# BiodataModular_008_SMD.net
KiCad netlist of a schematic drawn in EAGLE
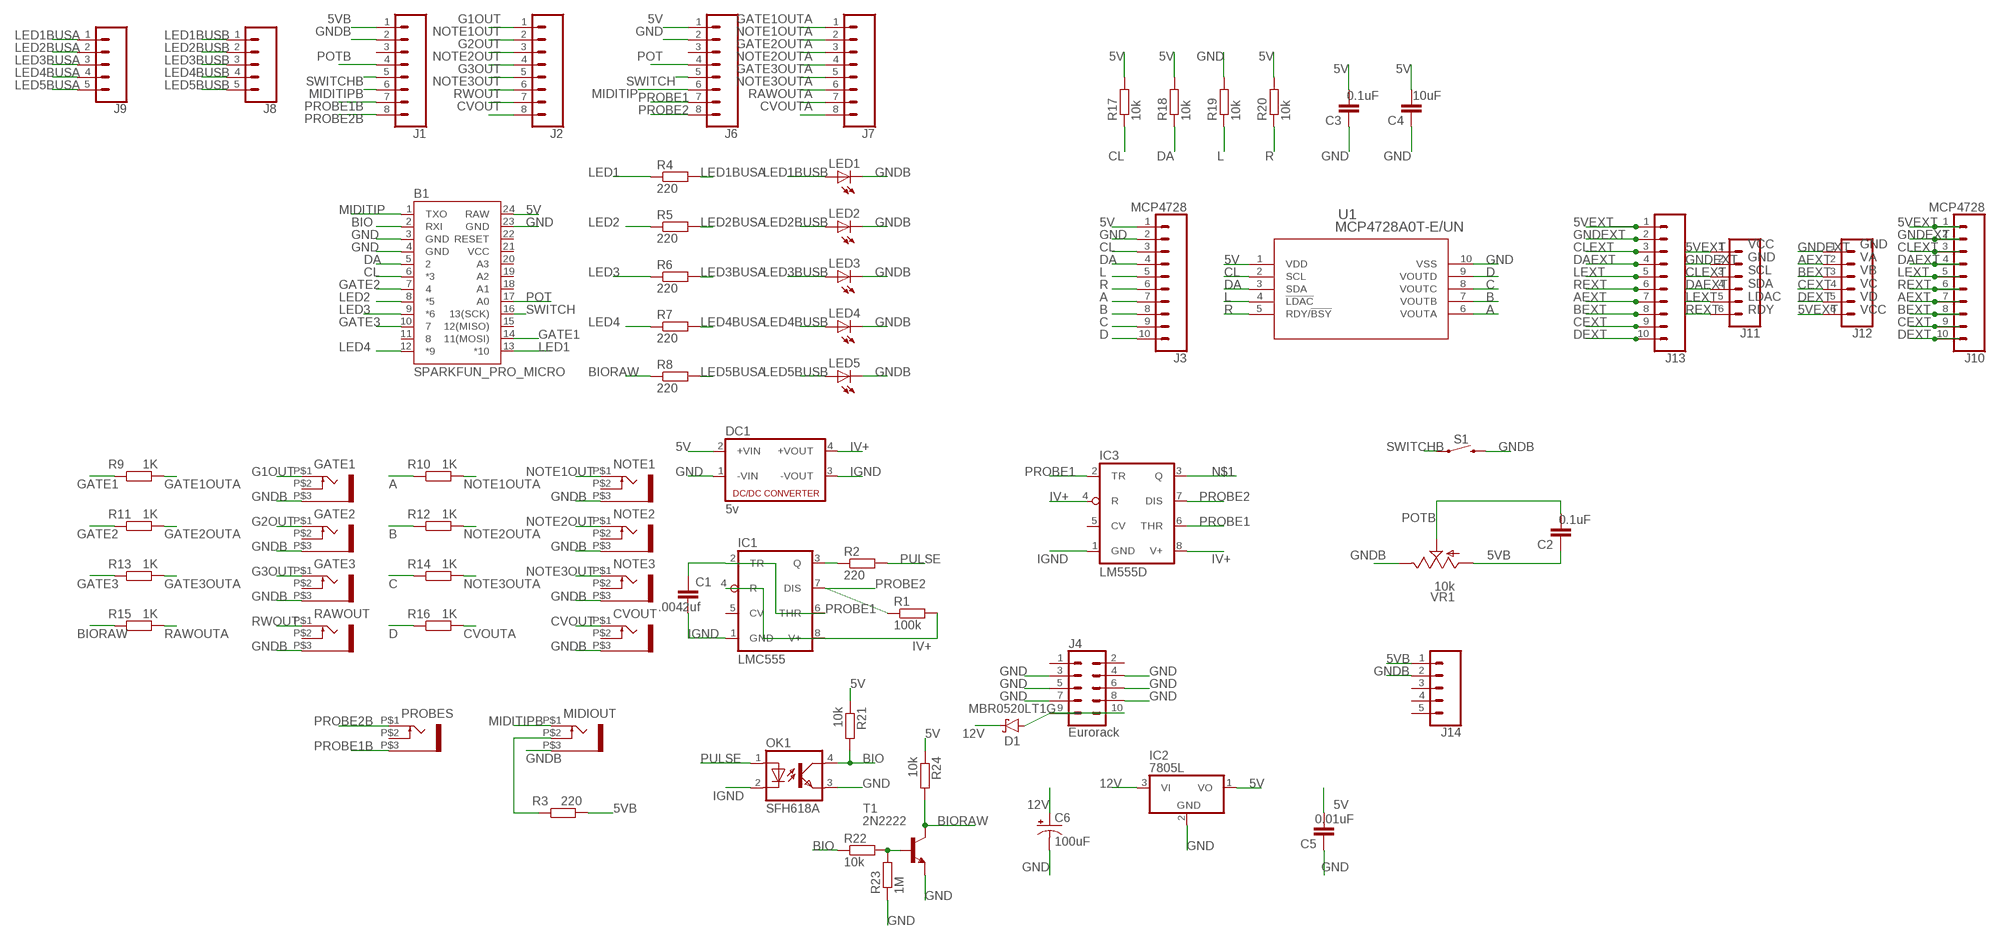
[diagram p0: schematic, sheet 1]

(export (version "E")
  (design (tool "Eeschema 10.0.6"))
  (components
    (comp (ref "B1")
      (value "SPARKFUN_PRO_MICRO")
      (footprint "eagle-import:SPARKFUN_PRO_MICRO")
      (libsource (lib "eagle-import") (part "SPARKFUN_PRO_MICRO"))
    )
    (comp (ref "C1")
      (value ".0042uf")
      (footprint "eagle-import:C1206")
      (libsource (lib "eagle-import") (part "C-EUC1206"))
    )
    (comp (ref "C2")
      (value "0.1uF")
      (footprint "eagle-import:C1206")
      (libsource (lib "eagle-import") (part "C-EUC1206"))
    )
    (comp (ref "C3")
      (value "0.1uF")
      (footprint "eagle-import:C1206")
      (libsource (lib "eagle-import") (part "C-EUC1206"))
    )
    (comp (ref "C4")
      (value "10uF")
      (footprint "eagle-import:C1206")
      (libsource (lib "eagle-import") (part "C-EUC1206"))
    )
    (comp (ref "C5")
      (value "0.01uF")
      (footprint "eagle-import:C1206")
      (libsource (lib "eagle-import") (part "C-EUC1206"))
    )
    (comp (ref "C6")
      (value "100uF")
      (footprint "eagle-import:B45181A")
      (libsource (lib "eagle-import") (part "CPOL-USB45181A"))
    )
    (comp (ref "CVOUT")
      (value "WQP-PJ301M-12_JACK")
      (footprint "eagle-import:WQP-PJ301M-12_JACK")
      (libsource (lib "eagle-import") (part "WQP-PJ301M-12_JACK"))
    )
    (comp (ref "D1")
      (value "MBR0520LT1G")
      (footprint "eagle-import:SODFL3718X115")
      (fields (field (name "MANUFACTURER") "ON Semiconductor"))
      (libsource (lib "eagle-import") (part "SCHOTTKY_DO-219MBR0520LT1G"))
    )
    (comp (ref "DC1")
      (value "5v")
      (footprint "eagle-import:NME")
      (fields (field (name "MF") "C & D TECHNOLOGIES, INC") (field (name "MPN") "NME1205D"))
      (libsource (lib "eagle-import") (part "NME"))
    )
    (comp (ref "GATE1")
      (value "WQP-PJ301M-12_JACK")
      (footprint "eagle-import:WQP-PJ301M-12_JACK")
      (libsource (lib "eagle-import") (part "WQP-PJ301M-12_JACK"))
    )
    (comp (ref "GATE2")
      (value "WQP-PJ301M-12_JACK")
      (footprint "eagle-import:WQP-PJ301M-12_JACK")
      (libsource (lib "eagle-import") (part "WQP-PJ301M-12_JACK"))
    )
    (comp (ref "GATE3")
      (value "WQP-PJ301M-12_JACK")
      (footprint "eagle-import:WQP-PJ301M-12_JACK")
      (libsource (lib "eagle-import") (part "WQP-PJ301M-12_JACK"))
    )
    (comp (ref "IC1")
      (value "LMC555")
      (footprint "eagle-import:DIL08")
      (libsource (lib "eagle-import") (part "linear_555NLM"))
    )
    (comp (ref "IC2")
      (value "7805L")
      (footprint "eagle-import:TO92")
      (libsource (lib "eagle-import") (part "78L05"))
    )
    (comp (ref "IC3")
      (value "LM555D")
      (footprint "eagle-import:SO08")
      (libsource (lib "eagle-import") (part "555DLM"))
    )
    (comp (ref "J1")
      (value "CONN_08\"")
      (footprint "eagle-import:1X08")
      (libsource (lib "eagle-import") (part "CONN_08{dblquote}"))
    )
    (comp (ref "J2")
      (value "CONN_08\"")
      (footprint "eagle-import:1X08")
      (libsource (lib "eagle-import") (part "CONN_08{dblquote}"))
    )
    (comp (ref "J3")
      (value "MCP4728")
      (footprint "eagle-import:1X10")
      (libsource (lib "eagle-import") (part "CONN_10{dblquote}"))
    )
    (comp (ref "J4")
      (value "Eurorack")
      (footprint "eagle-import:2X5")
      (libsource (lib "eagle-import") (part "CONN_05X2PTH"))
    )
    (comp (ref "J6")
      (value "CONN_08\"")
      (footprint "eagle-import:1X08")
      (libsource (lib "eagle-import") (part "CONN_08{dblquote}"))
    )
    (comp (ref "J7")
      (value "CONN_08\"")
      (footprint "eagle-import:1X08")
      (libsource (lib "eagle-import") (part "CONN_08{dblquote}"))
    )
    (comp (ref "J8")
      (value "CONN_05")
      (footprint "eagle-import:1X05")
      (libsource (lib "eagle-import") (part "CONN_05"))
    )
    (comp (ref "J9")
      (value "CONN_05")
      (footprint "eagle-import:1X05")
      (libsource (lib "eagle-import") (part "CONN_05"))
    )
    (comp (ref "J10")
      (value "MCP4728")
      (footprint "eagle-import:1X10")
      (libsource (lib "eagle-import") (part "CONN_10{dblquote}"))
    )
    (comp (ref "J11")
      (value "CONN_06SILK_FEMALE_PTH")
      (footprint "eagle-import:1X06")
      (libsource (lib "eagle-import") (part "CONN_06SILK_FEMALE_PTH"))
    )
    (comp (ref "J12")
      (value "CONN_06SILK_FEMALE_PTH")
      (footprint "eagle-import:1X06")
      (libsource (lib "eagle-import") (part "CONN_06SILK_FEMALE_PTH"))
    )
    (comp (ref "J13")
      (value "CONN_10SMD_MALE")
      (footprint "eagle-import:1X10_SMD_MALE")
      (libsource (lib "eagle-import") (part "CONN_10SMD_MALE"))
    )
    (comp (ref "J14")
      (value "CONN_05")
      (footprint "eagle-import:1X05")
      (libsource (lib "eagle-import") (part "CONN_05"))
    )
    (comp (ref "LED1")
      (value "LED3MM")
      (footprint "eagle-import:LED3MM")
      (libsource (lib "eagle-import") (part "LED3MM"))
    )
    (comp (ref "LED2")
      (value "LED3MM")
      (footprint "eagle-import:LED3MM")
      (libsource (lib "eagle-import") (part "LED3MM"))
    )
    (comp (ref "LED3")
      (value "LED3MM")
      (footprint "eagle-import:LED3MM")
      (libsource (lib "eagle-import") (part "LED3MM"))
    )
    (comp (ref "LED4")
      (value "LED3MM")
      (footprint "eagle-import:LED3MM")
      (libsource (lib "eagle-import") (part "LED3MM"))
    )
    (comp (ref "LED5")
      (value "LED3MM")
      (footprint "eagle-import:LED3MM")
      (libsource (lib "eagle-import") (part "LED3MM"))
    )
    (comp (ref "MIDIOUT")
      (value "WQP-PJ301M-12_JACK")
      (footprint "eagle-import:WQP-PJ301M-12_JACK")
      (libsource (lib "eagle-import") (part "WQP-PJ301M-12_JACK"))
    )
    (comp (ref "NOTE1")
      (value "WQP-PJ301M-12_JACK")
      (footprint "eagle-import:WQP-PJ301M-12_JACK")
      (libsource (lib "eagle-import") (part "WQP-PJ301M-12_JACK"))
    )
    (comp (ref "NOTE2")
      (value "WQP-PJ301M-12_JACK")
      (footprint "eagle-import:WQP-PJ301M-12_JACK")
      (libsource (lib "eagle-import") (part "WQP-PJ301M-12_JACK"))
    )
    (comp (ref "NOTE3")
      (value "WQP-PJ301M-12_JACK")
      (footprint "eagle-import:WQP-PJ301M-12_JACK")
      (libsource (lib "eagle-import") (part "WQP-PJ301M-12_JACK"))
    )
    (comp (ref "OK1")
      (value "SFH618A")
      (footprint "eagle-import:DIP4")
      (fields (field (name "MF") "VISHAY/TELEFUNKEN") (field (name "MPN") "SFH618A-5"))
      (libsource (lib "eagle-import") (part "SFH618?A-5"))
    )
    (comp (ref "PROBES")
      (value "WQP-PJ301M-12_JACK")
      (footprint "eagle-import:WQP-PJ301M-12_JACK")
      (libsource (lib "eagle-import") (part "WQP-PJ301M-12_JACK"))
    )
    (comp (ref "R1")
      (value "100k")
      (footprint "eagle-import:M1206")
      (libsource (lib "eagle-import") (part "R-EU_M1206"))
    )
    (comp (ref "R2")
      (value "220")
      (footprint "eagle-import:M1206")
      (libsource (lib "eagle-import") (part "R-EU_M1206"))
    )
    (comp (ref "R3")
      (value "220")
      (footprint "eagle-import:M1206")
      (libsource (lib "eagle-import") (part "R-EU_M1206"))
    )
    (comp (ref "R4")
      (value "220")
      (footprint "eagle-import:M1206")
      (libsource (lib "eagle-import") (part "R-EU_M1206"))
    )
    (comp (ref "R5")
      (value "220")
      (footprint "eagle-import:M1206")
      (libsource (lib "eagle-import") (part "R-EU_M1206"))
    )
    (comp (ref "R6")
      (value "220")
      (footprint "eagle-import:M1206")
      (libsource (lib "eagle-import") (part "R-EU_M1206"))
    )
    (comp (ref "R7")
      (value "220")
      (footprint "eagle-import:M1206")
      (libsource (lib "eagle-import") (part "R-EU_M1206"))
    )
    (comp (ref "R8")
      (value "220")
      (footprint "eagle-import:M1206")
      (libsource (lib "eagle-import") (part "R-EU_M1206"))
    )
    (comp (ref "R9")
      (value "1K")
      (footprint "eagle-import:M1206")
      (libsource (lib "eagle-import") (part "R-EU_M1206"))
    )
    (comp (ref "R10")
      (value "1K")
      (footprint "eagle-import:M1206")
      (libsource (lib "eagle-import") (part "R-EU_M1206"))
    )
    (comp (ref "R11")
      (value "1K")
      (footprint "eagle-import:M1206")
      (libsource (lib "eagle-import") (part "R-EU_M1206"))
    )
    (comp (ref "R12")
      (value "1K")
      (footprint "eagle-import:M1206")
      (libsource (lib "eagle-import") (part "R-EU_M1206"))
    )
    (comp (ref "R13")
      (value "1K")
      (footprint "eagle-import:M1206")
      (libsource (lib "eagle-import") (part "R-EU_M1206"))
    )
    (comp (ref "R14")
      (value "1K")
      (footprint "eagle-import:M1206")
      (libsource (lib "eagle-import") (part "R-EU_M1206"))
    )
    (comp (ref "R15")
      (value "1K")
      (footprint "eagle-import:M1206")
      (libsource (lib "eagle-import") (part "R-EU_M1206"))
    )
    (comp (ref "R16")
      (value "1K")
      (footprint "eagle-import:M1206")
      (libsource (lib "eagle-import") (part "R-EU_M1206"))
    )
    (comp (ref "R17")
      (value "10k")
      (footprint "eagle-import:M1206")
      (libsource (lib "eagle-import") (part "R-EU_M1206"))
    )
    (comp (ref "R18")
      (value "10k")
      (footprint "eagle-import:M1206")
      (libsource (lib "eagle-import") (part "R-EU_M1206"))
    )
    (comp (ref "R19")
      (value "10k")
      (footprint "eagle-import:M1206")
      (libsource (lib "eagle-import") (part "R-EU_M1206"))
    )
    (comp (ref "R20")
      (value "10k")
      (footprint "eagle-import:M1206")
      (libsource (lib "eagle-import") (part "R-EU_M1206"))
    )
    (comp (ref "R21")
      (value "10k")
      (footprint "eagle-import:M1206")
      (libsource (lib "eagle-import") (part "R-EU_M1206"))
    )
    (comp (ref "R22")
      (value "10k")
      (footprint "eagle-import:M1206")
      (libsource (lib "eagle-import") (part "R-EU_M1206"))
    )
    (comp (ref "R23")
      (value "1M")
      (footprint "eagle-import:M1206")
      (libsource (lib "eagle-import") (part "R-EU_M1206"))
    )
    (comp (ref "R24")
      (value "10k")
      (footprint "eagle-import:M1206")
      (libsource (lib "eagle-import") (part "R-EU_M1206"))
    )
    (comp (ref "RAWOUT")
      (value "WQP-PJ301M-12_JACK")
      (footprint "eagle-import:WQP-PJ301M-12_JACK")
      (libsource (lib "eagle-import") (part "WQP-PJ301M-12_JACK"))
    )
    (comp (ref "S1")
      (value "MOMENTARY-SWITCH-SPST-PTH-6.0MM")
      (footprint "eagle-import:TACTILE_SWITCH_PTH_6.0MM")
      (libsource (lib "eagle-import") (part "MOMENTARY-SWITCH-SPST-PTH-6.0MM"))
    )
    (comp (ref "T1")
      (value "2N2222")
      (footprint "eagle-import:TO92-EBC-OVAL")
      (libsource (lib "eagle-import") (part "2N2222"))
    )
    (comp (ref "U1")
      (value "MCP4728A0T-E/UN")
      (footprint "eagle-import:MSOP10_MC")
      (fields (field (name "MANUFACTURER_PART_NUMBER") "MCP4728A0TEUN"))
      (libsource (lib "eagle-import") (part "MCP4728A0T-E/UN"))
    )
    (comp (ref "VR1")
      (value "10k")
      (footprint "eagle-import:EVUFXM")
      (libsource (lib "eagle-import") (part "US-EVUMF3"))
    )
  )
  (nets
    (net (code "1") (name "/5V") (class "Default")
      (node (ref "B1") (pin "24") (pinfunction "RAW_24") (pintype "power_in"))
      (node (ref "C3") (pin "2") (pinfunction "2_2") (pintype "passive"))
      (node (ref "C4") (pin "2") (pinfunction "2_2") (pintype "passive"))
      (node (ref "C5") (pin "2") (pinfunction "2_2") (pintype "passive"))
      (node (ref "DC1") (pin "2") (pinfunction "+VIN_2") (pintype "passive"))
      (node (ref "IC2") (pin "1") (pinfunction "VO_1") (pintype "passive"))
      (node (ref "J3") (pin "1") (pinfunction "1_1") (pintype "passive"))
      (node (ref "J6") (pin "1") (pinfunction "1_1") (pintype "passive"))
      (node (ref "R17") (pin "2") (pinfunction "2_2") (pintype "passive"))
      (node (ref "R18") (pin "2") (pinfunction "2_2") (pintype "passive"))
      (node (ref "R20") (pin "2") (pinfunction "2_2") (pintype "passive"))
      (node (ref "R21") (pin "1") (pinfunction "1_1") (pintype "passive"))
      (node (ref "R24") (pin "1") (pinfunction "1_1") (pintype "passive"))
      (node (ref "U1") (pin "1") (pinfunction "VDD_1") (pintype "power_in"))
    )
    (net (code "2") (name "/5VB") (class "Default")
      (node (ref "C2") (pin "1") (pinfunction "1_1") (pintype "passive"))
      (node (ref "J1") (pin "1") (pinfunction "1_1") (pintype "passive"))
      (node (ref "J14") (pin "1") (pinfunction "1_1") (pintype "passive"))
      (node (ref "R3") (pin "2") (pinfunction "2_2") (pintype "passive"))
      (node (ref "VR1") (pin "1") (pinfunction "A_1") (pintype "passive"))
    )
    (net (code "3") (name "/5VEXT") (class "Default")
      (node (ref "J10") (pin "1") (pinfunction "1_1") (pintype "passive"))
      (node (ref "J11") (pin "1") (pinfunction "1_1") (pintype "passive"))
      (node (ref "J12") (pin "6") (pinfunction "6_6") (pintype "passive"))
      (node (ref "J13") (pin "1") (pinfunction "1_1") (pintype "passive"))
    )
    (net (code "4") (name "/12V") (class "Default")
      (node (ref "C6") (pin "+") (pinfunction "+_+") (pintype "passive"))
      (node (ref "D1") (pin "1") (pinfunction "C_1") (pintype "passive"))
      (node (ref "IC2") (pin "3") (pinfunction "VI_3") (pintype "input"))
    )
    (net (code "5") (name "/A") (class "Default")
      (node (ref "J3") (pin "7") (pinfunction "7_7") (pintype "passive"))
      (node (ref "R10") (pin "1") (pinfunction "1_1") (pintype "passive"))
      (node (ref "U1") (pin "6") (pinfunction "VOUTA_6") (pintype "output"))
    )
    (net (code "6") (name "/AEXT") (class "Default")
      (node (ref "J10") (pin "7") (pinfunction "7_7") (pintype "passive"))
      (node (ref "J12") (pin "2") (pinfunction "2_2") (pintype "passive"))
      (node (ref "J13") (pin "7") (pinfunction "7_7") (pintype "passive"))
    )
    (net (code "7") (name "/B") (class "Default")
      (node (ref "J3") (pin "8") (pinfunction "8_8") (pintype "passive"))
      (node (ref "R12") (pin "1") (pinfunction "1_1") (pintype "passive"))
      (node (ref "U1") (pin "7") (pinfunction "VOUTB_7") (pintype "output"))
    )
    (net (code "8") (name "/BEXT") (class "Default")
      (node (ref "J10") (pin "8") (pinfunction "8_8") (pintype "passive"))
      (node (ref "J12") (pin "3") (pinfunction "3_3") (pintype "passive"))
      (node (ref "J13") (pin "8") (pinfunction "8_8") (pintype "passive"))
    )
    (net (code "9") (name "/BIO") (class "Default")
      (node (ref "B1") (pin "2") (pinfunction "RXI_2") (pintype "bidirectional"))
      (node (ref "OK1") (pin "4") (pinfunction "COL_4") (pintype "passive"))
      (node (ref "R21") (pin "2") (pinfunction "2_2") (pintype "passive"))
      (node (ref "R22") (pin "1") (pinfunction "1_1") (pintype "passive"))
    )
    (net (code "10") (name "/BIORAW") (class "Default")
      (node (ref "R15") (pin "1") (pinfunction "1_1") (pintype "passive"))
      (node (ref "R24") (pin "2") (pinfunction "2_2") (pintype "passive"))
      (node (ref "R8") (pin "1") (pinfunction "1_1") (pintype "passive"))
      (node (ref "T1") (pin "C") (pinfunction "C_C") (pintype "passive"))
    )
    (net (code "11") (name "/C") (class "Default")
      (node (ref "J3") (pin "9") (pinfunction "9_9") (pintype "passive"))
      (node (ref "R14") (pin "1") (pinfunction "1_1") (pintype "passive"))
      (node (ref "U1") (pin "8") (pinfunction "VOUTC_8") (pintype "output"))
    )
    (net (code "12") (name "/CEXT") (class "Default")
      (node (ref "J10") (pin "9") (pinfunction "9_9") (pintype "passive"))
      (node (ref "J12") (pin "4") (pinfunction "4_4") (pintype "passive"))
      (node (ref "J13") (pin "9") (pinfunction "9_9") (pintype "passive"))
    )
    (net (code "13") (name "/CL") (class "Default")
      (node (ref "B1") (pin "6") (pinfunction "*3_6") (pintype "bidirectional"))
      (node (ref "J3") (pin "3") (pinfunction "3_3") (pintype "passive"))
      (node (ref "R17") (pin "1") (pinfunction "1_1") (pintype "passive"))
      (node (ref "U1") (pin "2") (pinfunction "SCL_2") (pintype "input"))
    )
    (net (code "14") (name "/CLEXT") (class "Default")
      (node (ref "J10") (pin "3") (pinfunction "3_3") (pintype "passive"))
      (node (ref "J11") (pin "3") (pinfunction "3_3") (pintype "passive"))
      (node (ref "J13") (pin "3") (pinfunction "3_3") (pintype "passive"))
    )
    (net (code "15") (name "/CVOUT") (class "Default")
      (node (ref "CVOUT") (pin "P$1") (pinfunction "2_P$1") (pintype "passive"))
      (node (ref "J2") (pin "8") (pinfunction "8_8") (pintype "passive"))
    )
    (net (code "16") (name "/CVOUTA") (class "Default")
      (node (ref "J7") (pin "8") (pinfunction "8_8") (pintype "passive"))
      (node (ref "R16") (pin "2") (pinfunction "2_2") (pintype "passive"))
    )
    (net (code "17") (name "/D") (class "Default")
      (node (ref "J3") (pin "10") (pinfunction "10_10") (pintype "passive"))
      (node (ref "R16") (pin "1") (pinfunction "1_1") (pintype "passive"))
      (node (ref "U1") (pin "9") (pinfunction "VOUTD_9") (pintype "output"))
    )
    (net (code "18") (name "/DA") (class "Default")
      (node (ref "B1") (pin "5") (pinfunction "2_5") (pintype "bidirectional"))
      (node (ref "J3") (pin "4") (pinfunction "4_4") (pintype "passive"))
      (node (ref "R18") (pin "1") (pinfunction "1_1") (pintype "passive"))
      (node (ref "U1") (pin "3") (pinfunction "SDA_3") (pintype "bidirectional"))
    )
    (net (code "19") (name "/DAEXT") (class "Default")
      (node (ref "J10") (pin "4") (pinfunction "4_4") (pintype "passive"))
      (node (ref "J11") (pin "4") (pinfunction "4_4") (pintype "passive"))
      (node (ref "J13") (pin "4") (pinfunction "4_4") (pintype "passive"))
    )
    (net (code "20") (name "/DEXT") (class "Default")
      (node (ref "J10") (pin "10") (pinfunction "10_10") (pintype "passive"))
      (node (ref "J12") (pin "5") (pinfunction "5_5") (pintype "passive"))
      (node (ref "J13") (pin "10") (pinfunction "10_10") (pintype "passive"))
    )
    (net (code "21") (name "/G1OUT") (class "Default")
      (node (ref "GATE1") (pin "P$1") (pinfunction "2_P$1") (pintype "passive"))
      (node (ref "J2") (pin "1") (pinfunction "1_1") (pintype "passive"))
    )
    (net (code "22") (name "/G2OUT") (class "Default")
      (node (ref "GATE2") (pin "P$1") (pinfunction "2_P$1") (pintype "passive"))
      (node (ref "J2") (pin "3") (pinfunction "3_3") (pintype "passive"))
    )
    (net (code "23") (name "/G3OUT") (class "Default")
      (node (ref "GATE3") (pin "P$1") (pinfunction "2_P$1") (pintype "passive"))
      (node (ref "J2") (pin "5") (pinfunction "5_5") (pintype "passive"))
    )
    (net (code "24") (name "/GATE1") (class "Default")
      (node (ref "B1") (pin "14") (pinfunction "11(MOSI)_14") (pintype "bidirectional"))
      (node (ref "R9") (pin "1") (pinfunction "1_1") (pintype "passive"))
    )
    (net (code "25") (name "/GATE1OUTA") (class "Default")
      (node (ref "J7") (pin "1") (pinfunction "1_1") (pintype "passive"))
      (node (ref "R9") (pin "2") (pinfunction "2_2") (pintype "passive"))
    )
    (net (code "26") (name "/GATE2") (class "Default")
      (node (ref "B1") (pin "7") (pinfunction "4_7") (pintype "bidirectional"))
      (node (ref "R11") (pin "1") (pinfunction "1_1") (pintype "passive"))
    )
    (net (code "27") (name "/GATE2OUTA") (class "Default")
      (node (ref "J7") (pin "3") (pinfunction "3_3") (pintype "passive"))
      (node (ref "R11") (pin "2") (pinfunction "2_2") (pintype "passive"))
    )
    (net (code "28") (name "/GATE3") (class "Default")
      (node (ref "B1") (pin "10") (pinfunction "7_10") (pintype "bidirectional"))
      (node (ref "R13") (pin "1") (pinfunction "1_1") (pintype "passive"))
    )
    (net (code "29") (name "/GATE3OUTA") (class "Default")
      (node (ref "J7") (pin "5") (pinfunction "5_5") (pintype "passive"))
      (node (ref "R13") (pin "2") (pinfunction "2_2") (pintype "passive"))
    )
    (net (code "30") (name "/GND") (class "Default")
      (node (ref "B1") (pin "23") (pinfunction "GND_23") (pintype "power_in"))
      (node (ref "B1") (pin "3") (pinfunction "GND_3") (pintype "power_in"))
      (node (ref "B1") (pin "4") (pinfunction "GND_4") (pintype "power_in"))
      (node (ref "C3") (pin "1") (pinfunction "1_1") (pintype "passive"))
      (node (ref "C4") (pin "1") (pinfunction "1_1") (pintype "passive"))
      (node (ref "C5") (pin "1") (pinfunction "1_1") (pintype "passive"))
      (node (ref "C6") (pin "-") (pinfunction "-_-") (pintype "passive"))
      (node (ref "DC1") (pin "1") (pinfunction "-VIN_1") (pintype "passive"))
      (node (ref "IC2") (pin "2") (pinfunction "GND_2") (pintype "passive"))
      (node (ref "J3") (pin "2") (pinfunction "2_2") (pintype "passive"))
      (node (ref "J4") (pin "3") (pinfunction "3_3") (pintype "passive"))
      (node (ref "J4") (pin "4") (pinfunction "4_4") (pintype "passive"))
      (node (ref "J4") (pin "5") (pinfunction "5_5") (pintype "passive"))
      (node (ref "J4") (pin "6") (pinfunction "6_6") (pintype "passive"))
      (node (ref "J4") (pin "7") (pinfunction "7_7") (pintype "passive"))
      (node (ref "J4") (pin "8") (pinfunction "8_8") (pintype "passive"))
      (node (ref "J6") (pin "2") (pinfunction "2_2") (pintype "passive"))
      (node (ref "OK1") (pin "3") (pinfunction "EMIT_3") (pintype "passive"))
      (node (ref "R19") (pin "2") (pinfunction "2_2") (pintype "passive"))
      (node (ref "R23") (pin "1") (pinfunction "1_1") (pintype "passive"))
      (node (ref "T1") (pin "E") (pinfunction "E_E") (pintype "passive"))
      (node (ref "U1") (pin "10") (pinfunction "VSS_10") (pintype "power_in"))
    )
    (net (code "31") (name "/GNDB") (class "Default")
      (node (ref "CVOUT") (pin "P$3") (pinfunction "1_P$3") (pintype "passive"))
      (node (ref "GATE1") (pin "P$3") (pinfunction "1_P$3") (pintype "passive"))
      (node (ref "GATE2") (pin "P$3") (pinfunction "1_P$3") (pintype "passive"))
      (node (ref "GATE3") (pin "P$3") (pinfunction "1_P$3") (pintype "passive"))
      (node (ref "J1") (pin "2") (pinfunction "2_2") (pintype "passive"))
      (node (ref "J14") (pin "2") (pinfunction "2_2") (pintype "passive"))
      (node (ref "LED1") (pin "K") (pinfunction "C_K") (pintype "passive"))
      (node (ref "LED2") (pin "K") (pinfunction "C_K") (pintype "passive"))
      (node (ref "LED3") (pin "K") (pinfunction "C_K") (pintype "passive"))
      (node (ref "LED4") (pin "K") (pinfunction "C_K") (pintype "passive"))
      (node (ref "LED5") (pin "K") (pinfunction "C_K") (pintype "passive"))
      (node (ref "MIDIOUT") (pin "P$3") (pinfunction "1_P$3") (pintype "passive"))
      (node (ref "NOTE1") (pin "P$3") (pinfunction "1_P$3") (pintype "passive"))
      (node (ref "NOTE2") (pin "P$3") (pinfunction "1_P$3") (pintype "passive"))
      (node (ref "NOTE3") (pin "P$3") (pinfunction "1_P$3") (pintype "passive"))
      (node (ref "RAWOUT") (pin "P$3") (pinfunction "1_P$3") (pintype "passive"))
      (node (ref "S1") (pin "3") (pinfunction "2_3") (pintype "passive"))
      (node (ref "VR1") (pin "3") (pinfunction "E_3") (pintype "passive"))
    )
    (net (code "32") (name "/GNDEXT") (class "Default")
      (node (ref "J10") (pin "2") (pinfunction "2_2") (pintype "passive"))
      (node (ref "J11") (pin "2") (pinfunction "2_2") (pintype "passive"))
      (node (ref "J12") (pin "1") (pinfunction "1_1") (pintype "passive"))
      (node (ref "J13") (pin "2") (pinfunction "2_2") (pintype "passive"))
    )
    (net (code "33") (name "/IGND") (class "Default")
      (node (ref "C1") (pin "2") (pinfunction "2_2") (pintype "passive"))
      (node (ref "DC1") (pin "3") (pinfunction "-VOUT_3") (pintype "passive"))
      (node (ref "IC1") (pin "1") (pinfunction "GND_1") (pintype "power_in"))
      (node (ref "IC3") (pin "1") (pinfunction "GND_1") (pintype "power_in"))
      (node (ref "OK1") (pin "2") (pinfunction "C_2") (pintype "passive"))
    )
    (net (code "34") (name "/IV+") (class "Default")
      (node (ref "DC1") (pin "4") (pinfunction "+VOUT_4") (pintype "passive"))
      (node (ref "IC1") (pin "4") (pinfunction "R_4") (pintype "input"))
      (node (ref "IC1") (pin "8") (pinfunction "V+_8") (pintype "power_in"))
      (node (ref "IC3") (pin "4") (pinfunction "R_4") (pintype "input"))
      (node (ref "IC3") (pin "8") (pinfunction "V+_8") (pintype "power_in"))
      (node (ref "R1") (pin "2") (pinfunction "2_2") (pintype "passive"))
    )
    (net (code "35") (name "/L") (class "Default")
      (node (ref "J3") (pin "5") (pinfunction "5_5") (pintype "passive"))
      (node (ref "R19") (pin "1") (pinfunction "1_1") (pintype "passive"))
      (node (ref "U1") (pin "4") (pinfunction "~{LDAC}_4") (pintype "input"))
    )
    (net (code "36") (name "/LED1") (class "Default")
      (node (ref "B1") (pin "13") (pinfunction "*10_13") (pintype "bidirectional"))
      (node (ref "R4") (pin "1") (pinfunction "1_1") (pintype "passive"))
    )
    (net (code "37") (name "/LED1BUSA") (class "Default")
      (node (ref "J9") (pin "1") (pinfunction "1_1") (pintype "passive"))
      (node (ref "R4") (pin "2") (pinfunction "2_2") (pintype "passive"))
    )
    (net (code "38") (name "/LED1BUSB") (class "Default")
      (node (ref "J8") (pin "1") (pinfunction "1_1") (pintype "passive"))
      (node (ref "LED1") (pin "A") (pinfunction "A_A") (pintype "passive"))
    )
    (net (code "39") (name "/LED2") (class "Default")
      (node (ref "B1") (pin "8") (pinfunction "*5_8") (pintype "bidirectional"))
      (node (ref "R5") (pin "1") (pinfunction "1_1") (pintype "passive"))
    )
    (net (code "40") (name "/LED2BUSA") (class "Default")
      (node (ref "J9") (pin "2") (pinfunction "2_2") (pintype "passive"))
      (node (ref "R5") (pin "2") (pinfunction "2_2") (pintype "passive"))
    )
    (net (code "41") (name "/LED2BUSB") (class "Default")
      (node (ref "J8") (pin "2") (pinfunction "2_2") (pintype "passive"))
      (node (ref "LED2") (pin "A") (pinfunction "A_A") (pintype "passive"))
    )
    (net (code "42") (name "/LED3") (class "Default")
      (node (ref "B1") (pin "9") (pinfunction "*6_9") (pintype "bidirectional"))
      (node (ref "R6") (pin "1") (pinfunction "1_1") (pintype "passive"))
    )
    (net (code "43") (name "/LED3BUSA") (class "Default")
      (node (ref "J9") (pin "3") (pinfunction "3_3") (pintype "passive"))
      (node (ref "R6") (pin "2") (pinfunction "2_2") (pintype "passive"))
    )
    (net (code "44") (name "/LED3BUSB") (class "Default")
      (node (ref "J8") (pin "3") (pinfunction "3_3") (pintype "passive"))
      (node (ref "LED3") (pin "A") (pinfunction "A_A") (pintype "passive"))
    )
    (net (code "45") (name "/LED4") (class "Default")
      (node (ref "B1") (pin "12") (pinfunction "*9_12") (pintype "bidirectional"))
      (node (ref "R7") (pin "1") (pinfunction "1_1") (pintype "passive"))
    )
    (net (code "46") (name "/LED4BUSA") (class "Default")
      (node (ref "J9") (pin "4") (pinfunction "4_4") (pintype "passive"))
      (node (ref "R7") (pin "2") (pinfunction "2_2") (pintype "passive"))
    )
    (net (code "47") (name "/LED4BUSB") (class "Default")
      (node (ref "J8") (pin "4") (pinfunction "4_4") (pintype "passive"))
      (node (ref "LED4") (pin "A") (pinfunction "A_A") (pintype "passive"))
    )
    (net (code "48") (name "/LED5BUSA") (class "Default")
      (node (ref "J9") (pin "5") (pinfunction "5_5") (pintype "passive"))
      (node (ref "R8") (pin "2") (pinfunction "2_2") (pintype "passive"))
    )
    (net (code "49") (name "/LED5BUSB") (class "Default")
      (node (ref "J8") (pin "5") (pinfunction "5_5") (pintype "passive"))
      (node (ref "LED5") (pin "A") (pinfunction "A_A") (pintype "passive"))
    )
    (net (code "50") (name "/LEXT") (class "Default")
      (node (ref "J10") (pin "5") (pinfunction "5_5") (pintype "passive"))
      (node (ref "J11") (pin "5") (pinfunction "5_5") (pintype "passive"))
      (node (ref "J13") (pin "5") (pinfunction "5_5") (pintype "passive"))
    )
    (net (code "51") (name "/MIDITIP") (class "Default")
      (node (ref "B1") (pin "1") (pinfunction "TXO_1") (pintype "bidirectional"))
      (node (ref "J6") (pin "6") (pinfunction "6_6") (pintype "passive"))
    )
    (net (code "52") (name "/MIDITIPB") (class "Default")
      (node (ref "J1") (pin "6") (pinfunction "6_6") (pintype "passive"))
      (node (ref "MIDIOUT") (pin "P$1") (pinfunction "2_P$1") (pintype "passive"))
    )
    (net (code "53") (name "/N$1") (class "Default")
      (node (ref "IC1") (pin "3") (pinfunction "Q_3") (pintype "output"))
      (node (ref "IC3") (pin "3") (pinfunction "Q_3") (pintype "output"))
      (node (ref "R2") (pin "1") (pinfunction "1_1") (pintype "passive"))
    )
    (net (code "54") (name "/NOTE1OUT") (class "Default")
      (node (ref "J2") (pin "2") (pinfunction "2_2") (pintype "passive"))
      (node (ref "NOTE1") (pin "P$1") (pinfunction "2_P$1") (pintype "passive"))
    )
    (net (code "55") (name "/NOTE1OUTA") (class "Default")
      (node (ref "J7") (pin "2") (pinfunction "2_2") (pintype "passive"))
      (node (ref "R10") (pin "2") (pinfunction "2_2") (pintype "passive"))
    )
    (net (code "56") (name "/NOTE2OUT") (class "Default")
      (node (ref "J2") (pin "4") (pinfunction "4_4") (pintype "passive"))
      (node (ref "NOTE2") (pin "P$1") (pinfunction "2_P$1") (pintype "passive"))
    )
    (net (code "57") (name "/NOTE2OUTA") (class "Default")
      (node (ref "J7") (pin "4") (pinfunction "4_4") (pintype "passive"))
      (node (ref "R12") (pin "2") (pinfunction "2_2") (pintype "passive"))
    )
    (net (code "58") (name "/NOTE3OUT") (class "Default")
      (node (ref "J2") (pin "6") (pinfunction "6_6") (pintype "passive"))
      (node (ref "NOTE3") (pin "P$1") (pinfunction "2_P$1") (pintype "passive"))
    )
    (net (code "59") (name "/NOTE3OUTA") (class "Default")
      (node (ref "J7") (pin "6") (pinfunction "6_6") (pintype "passive"))
      (node (ref "R14") (pin "2") (pinfunction "2_2") (pintype "passive"))
    )
    (net (code "60") (name "/POT") (class "Default")
      (node (ref "B1") (pin "17") (pinfunction "A0_17") (pintype "bidirectional"))
      (node (ref "J6") (pin "4") (pinfunction "4_4") (pintype "passive"))
    )
    (net (code "61") (name "/POTB") (class "Default")
      (node (ref "C2") (pin "2") (pinfunction "2_2") (pintype "passive"))
      (node (ref "J1") (pin "4") (pinfunction "4_4") (pintype "passive"))
      (node (ref "VR1") (pin "2") (pinfunction "S_2") (pintype "passive"))
    )
    (net (code "62") (name "/PROBE1") (class "Default")
      (node (ref "C1") (pin "1") (pinfunction "1_1") (pintype "passive"))
      (node (ref "IC1") (pin "2") (pinfunction "TR_2") (pintype "input"))
      (node (ref "IC1") (pin "6") (pinfunction "THR_6") (pintype "input"))
      (node (ref "IC3") (pin "2") (pinfunction "TR_2") (pintype "input"))
      (node (ref "IC3") (pin "6") (pinfunction "THR_6") (pintype "input"))
      (node (ref "J6") (pin "7") (pinfunction "7_7") (pintype "passive"))
    )
    (net (code "63") (name "/PROBE1B") (class "Default")
      (node (ref "J1") (pin "7") (pinfunction "7_7") (pintype "passive"))
      (node (ref "PROBES") (pin "P$3") (pinfunction "1_P$3") (pintype "passive"))
    )
    (net (code "64") (name "/PROBE2") (class "Default")
      (node (ref "IC1") (pin "7") (pinfunction "DIS_7") (pintype "input"))
      (node (ref "IC3") (pin "7") (pinfunction "DIS_7") (pintype "input"))
      (node (ref "J6") (pin "8") (pinfunction "8_8") (pintype "passive"))
      (node (ref "R1") (pin "1") (pinfunction "1_1") (pintype "passive"))
    )
    (net (code "65") (name "/PROBE2B") (class "Default")
      (node (ref "J1") (pin "8") (pinfunction "8_8") (pintype "passive"))
      (node (ref "PROBES") (pin "P$1") (pinfunction "2_P$1") (pintype "passive"))
    )
    (net (code "66") (name "/PULSE") (class "Default")
      (node (ref "OK1") (pin "1") (pinfunction "A_1") (pintype "passive"))
      (node (ref "R2") (pin "2") (pinfunction "2_2") (pintype "passive"))
    )
    (net (code "67") (name "/R") (class "Default")
      (node (ref "J3") (pin "6") (pinfunction "6_6") (pintype "passive"))
      (node (ref "R20") (pin "1") (pinfunction "1_1") (pintype "passive"))
      (node (ref "U1") (pin "5") (pinfunction "RDY/~{BSY}_5") (pintype "output"))
    )
    (net (code "68") (name "/RAWOUTA") (class "Default")
      (node (ref "J7") (pin "7") (pinfunction "7_7") (pintype "passive"))
      (node (ref "R15") (pin "2") (pinfunction "2_2") (pintype "passive"))
    )
    (net (code "69") (name "/REXT") (class "Default")
      (node (ref "J10") (pin "6") (pinfunction "6_6") (pintype "passive"))
      (node (ref "J11") (pin "6") (pinfunction "6_6") (pintype "passive"))
      (node (ref "J13") (pin "6") (pinfunction "6_6") (pintype "passive"))
    )
    (net (code "70") (name "/RWOUT") (class "Default")
      (node (ref "J2") (pin "7") (pinfunction "7_7") (pintype "passive"))
      (node (ref "RAWOUT") (pin "P$1") (pinfunction "2_P$1") (pintype "passive"))
    )
    (net (code "71") (name "/SWITCH") (class "Default")
      (node (ref "B1") (pin "16") (pinfunction "13(SCK)_16") (pintype "bidirectional"))
      (node (ref "J6") (pin "5") (pinfunction "5_5") (pintype "passive"))
    )
    (net (code "72") (name "/SWITCHB") (class "Default")
      (node (ref "J1") (pin "5") (pinfunction "5_5") (pintype "passive"))
      (node (ref "S1") (pin "1") (pinfunction "1_1") (pintype "passive"))
    )
    (net (code "73") (name "/VCC") (class "Default")
      (node (ref "B1") (pin "21") (pinfunction "VCC_21") (pintype "power_in"))
    )
    (net (code "74") (name "Net-(D1-A)") (class "Default")
      (node (ref "D1") (pin "2") (pinfunction "A_2") (pintype "passive"))
      (node (ref "J4") (pin "10") (pinfunction "10_10") (pintype "passive"))
      (node (ref "J4") (pin "9") (pinfunction "9_9") (pintype "passive"))
    )
    (net (code "75") (name "Net-(MIDIOUT-3)") (class "Default")
      (node (ref "MIDIOUT") (pin "P$2") (pinfunction "3_P$2") (pintype "passive"))
      (node (ref "R3") (pin "1") (pinfunction "1_1") (pintype "passive"))
    )
    (net (code "76") (name "Net-(R22-Pad2)") (class "Default")
      (node (ref "R22") (pin "2") (pinfunction "2_2") (pintype "passive"))
      (node (ref "R23") (pin "2") (pinfunction "2_2") (pintype "passive"))
      (node (ref "T1") (pin "B") (pinfunction "B_B") (pintype "passive"))
    )
    (net (code "77") (name "unconnected-(B1-8-Pad11)") (class "Default")
      (node (ref "B1") (pin "11") (pinfunction "8_11") (pintype "bidirectional"))
    )
    (net (code "78") (name "unconnected-(B1-12(MISO)-Pad15)") (class "Default")
      (node (ref "B1") (pin "15") (pinfunction "12(MISO)_15") (pintype "bidirectional"))
    )
    (net (code "79") (name "unconnected-(B1-A1-Pad18)") (class "Default")
      (node (ref "B1") (pin "18") (pinfunction "A1_18") (pintype "bidirectional"))
    )
    (net (code "80") (name "unconnected-(B1-A2-Pad19)") (class "Default")
      (node (ref "B1") (pin "19") (pinfunction "A2_19") (pintype "bidirectional"))
    )
    (net (code "81") (name "unconnected-(B1-A3-Pad20)") (class "Default")
      (node (ref "B1") (pin "20") (pinfunction "A3_20") (pintype "bidirectional"))
    )
    (net (code "82") (name "unconnected-(B1-RESET-Pad22)") (class "Default")
      (node (ref "B1") (pin "22") (pinfunction "RESET_22") (pintype "bidirectional"))
    )
    (net (code "83") (name "unconnected-(CVOUT-3-PadP$2)") (class "Default")
      (node (ref "CVOUT") (pin "P$2") (pinfunction "3_P$2") (pintype "passive"))
    )
    (net (code "84") (name "unconnected-(GATE1-3-PadP$2)") (class "Default")
      (node (ref "GATE1") (pin "P$2") (pinfunction "3_P$2") (pintype "passive"))
    )
    (net (code "85") (name "unconnected-(GATE2-3-PadP$2)") (class "Default")
      (node (ref "GATE2") (pin "P$2") (pinfunction "3_P$2") (pintype "passive"))
    )
    (net (code "86") (name "unconnected-(GATE3-3-PadP$2)") (class "Default")
      (node (ref "GATE3") (pin "P$2") (pinfunction "3_P$2") (pintype "passive"))
    )
    (net (code "87") (name "unconnected-(IC1-CV-Pad5)") (class "Default")
      (node (ref "IC1") (pin "5") (pinfunction "CV_5") (pintype "input"))
    )
    (net (code "88") (name "unconnected-(IC3-CV-Pad5)") (class "Default")
      (node (ref "IC3") (pin "5") (pinfunction "CV_5") (pintype "input"))
    )
    (net (code "89") (name "unconnected-(J1-Pad3)") (class "Default")
      (node (ref "J1") (pin "3") (pinfunction "3_3") (pintype "passive"))
    )
    (net (code "90") (name "unconnected-(J4-Pad1)") (class "Default")
      (node (ref "J4") (pin "1") (pinfunction "1_1") (pintype "passive"))
    )
    (net (code "91") (name "unconnected-(J4-Pad2)") (class "Default")
      (node (ref "J4") (pin "2") (pinfunction "2_2") (pintype "passive"))
    )
    (net (code "92") (name "unconnected-(J6-Pad3)") (class "Default")
      (node (ref "J6") (pin "3") (pinfunction "3_3") (pintype "passive"))
    )
    (net (code "93") (name "unconnected-(J14-Pad3)") (class "Default")
      (node (ref "J14") (pin "3") (pinfunction "3_3") (pintype "passive"))
    )
    (net (code "94") (name "unconnected-(J14-Pad4)") (class "Default")
      (node (ref "J14") (pin "4") (pinfunction "4_4") (pintype "passive"))
    )
    (net (code "95") (name "unconnected-(J14-Pad5)") (class "Default")
      (node (ref "J14") (pin "5") (pinfunction "5_5") (pintype "passive"))
    )
    (net (code "96") (name "unconnected-(NOTE1-3-PadP$2)") (class "Default")
      (node (ref "NOTE1") (pin "P$2") (pinfunction "3_P$2") (pintype "passive"))
    )
    (net (code "97") (name "unconnected-(NOTE2-3-PadP$2)") (class "Default")
      (node (ref "NOTE2") (pin "P$2") (pinfunction "3_P$2") (pintype "passive"))
    )
    (net (code "98") (name "unconnected-(NOTE3-3-PadP$2)") (class "Default")
      (node (ref "NOTE3") (pin "P$2") (pinfunction "3_P$2") (pintype "passive"))
    )
    (net (code "99") (name "unconnected-(PROBES-3-PadP$2)") (class "Default")
      (node (ref "PROBES") (pin "P$2") (pinfunction "3_P$2") (pintype "passive"))
    )
    (net (code "100") (name "unconnected-(RAWOUT-3-PadP$2)") (class "Default")
      (node (ref "RAWOUT") (pin "P$2") (pinfunction "3_P$2") (pintype "passive"))
    )
  )
)
